# Thermostat_EEM.net
KiCad netlist of a schematic drawn in Altium Designer
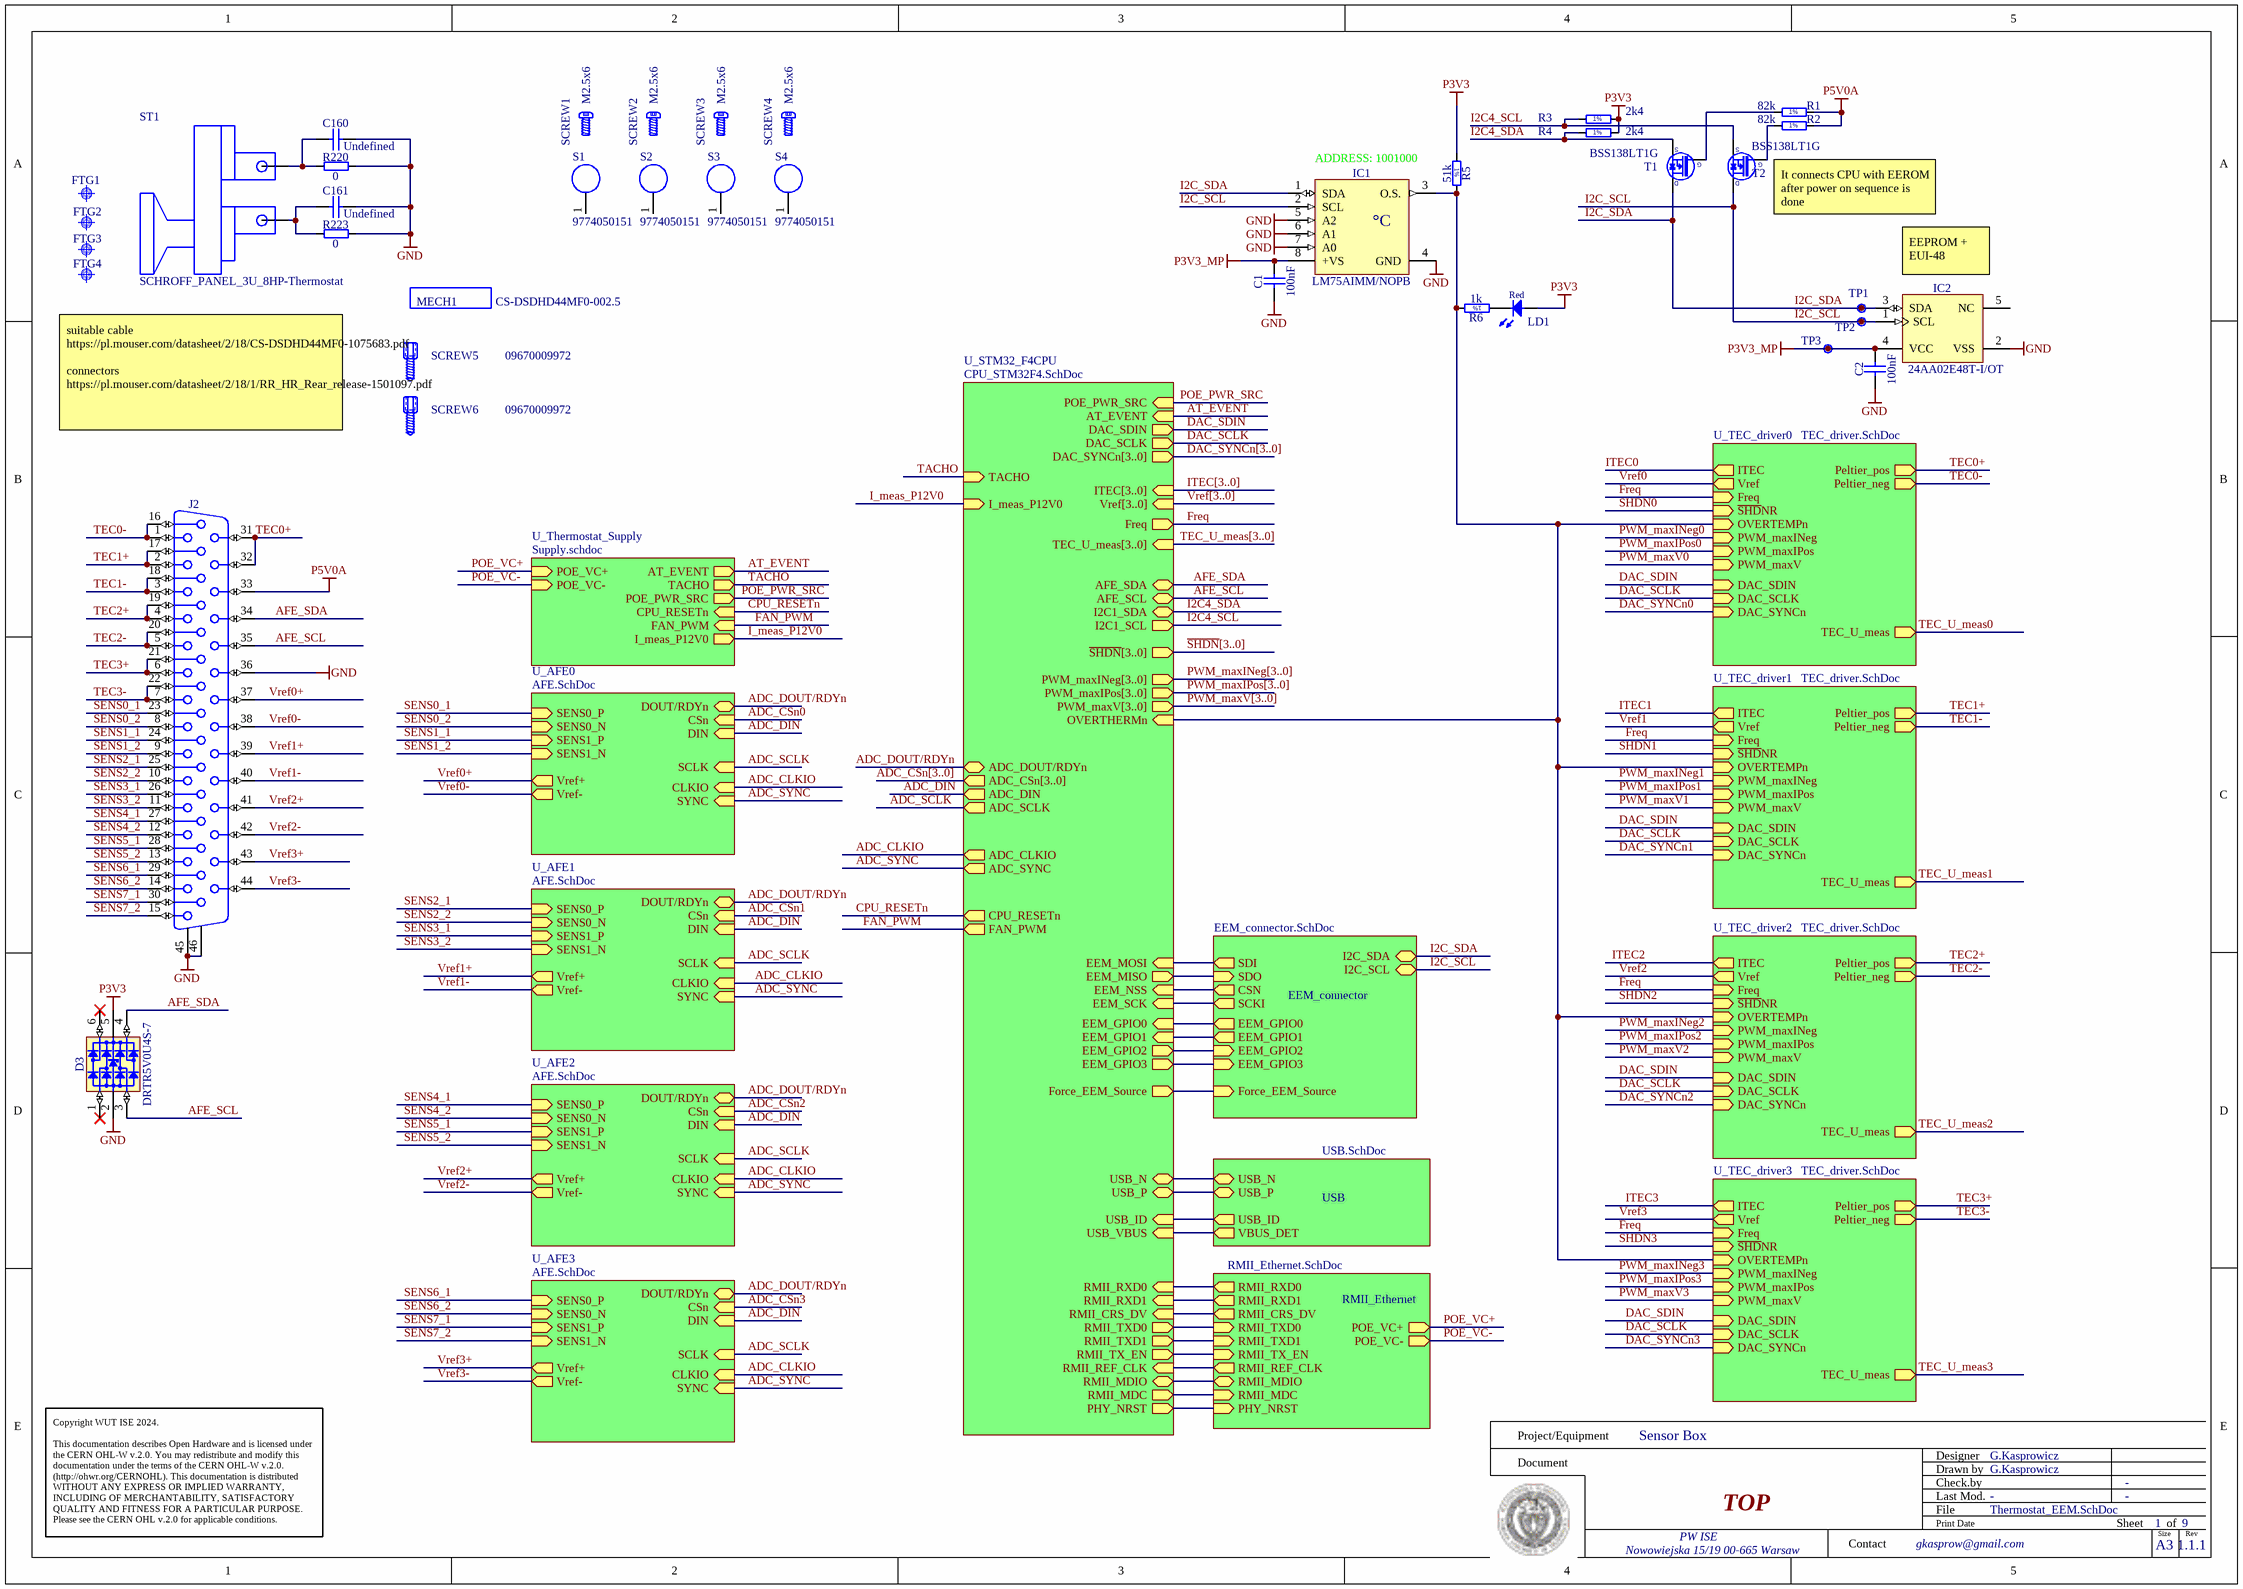
[diagram p0: Thermostat_EEM.SchDoc]

(export (version "E")
  (design (tool "Eeschema 10.0.6"))
  (components
    (comp (ref "C1")
      (value "100nF")
      (footprint "CAPC1005X55N")
      (description "Non-polarised capacitor")
      (fields
        (field (name "PART NUMBER") "CC0402_100NF_16V_10%_X5R")
        (field (name "VOLTAGE") "16V")
        (field (name "AUTHOR") "CERN DEM JLC")
      )
      (libsource (lib "Capacitors") (part "Capacitor - non polarized"))
    )
    (comp (ref "C2")
      (value "100nF")
      (footprint "CAPC1005X55N")
      (description "Non-polarised capacitor")
      (fields
        (field (name "PART NUMBER") "CC0402_100NF_16V_10%_X5R")
        (field (name "VOLTAGE") "16V")
        (field (name "AUTHOR") "CERN DEM JLC")
      )
      (libsource (lib "Capacitors") (part "Capacitor - non polarized"))
    )
    (comp (ref "C160")
      (value "Undefined")
      (footprint "CAPC2012X135N")
      (description "Non-polarised capacitor")
      (fields (field (name "PART NUMBER") "CC0805_NO-VALUE") (field (name "AUTHOR") "CERN DEM JLC"))
      (libsource (lib "Capacitors") (part "Capacitor - non polarized"))
    )
    (comp (ref "C161")
      (value "Undefined")
      (footprint "CAPC2012X135N")
      (description "Non-polarised capacitor")
      (fields (field (name "PART NUMBER") "CC0805_NO-VALUE") (field (name "AUTHOR") "CERN DEM JLC"))
      (libsource (lib "Capacitors") (part "Capacitor - non polarized"))
    )
    (comp (ref "D3")
      (value "DRTR5V0U4S-7")
      (footprint "SOT65P210X110-6N")
      (description "Integrated Quad Ultra-Low Capacitance ESD Protection")
      (fields (field (name "MANUFACTURER") "DIODES") (field (name "AUTHOR") "GK"))
      (libsource (lib "Diodes") (part "D_TVS_DRTR5V0U4S-7"))
    )
    (comp (ref "FTG1")
      (value "Use only in PCB")
      (footprint "FIDUCIAL_TOP_S100-200")
      (description "Fiducial Target")
      (fields (field (name "PART NUMBER") "FIDUCIAL_TARGET_S100-200") (field (name "AUTHOR") "CERN DEM JLC"))
      (libsource (lib "Eletro-mechanical") (part "Fiducial Target"))
    )
    (comp (ref "FTG2")
      (value "Use only in PCB")
      (footprint "FIDUCIAL_TOP_S100-200")
      (description "Fiducial Target")
      (fields (field (name "PART NUMBER") "FIDUCIAL_TARGET_S100-200") (field (name "AUTHOR") "CERN DEM JLC"))
      (libsource (lib "Eletro-mechanical") (part "Fiducial Target"))
    )
    (comp (ref "FTG3")
      (value "Use only in PCB")
      (footprint "FIDUCIAL_TOP_S100-200")
      (description "Fiducial Target")
      (fields (field (name "PART NUMBER") "FIDUCIAL_TARGET_S100-200") (field (name "AUTHOR") "CERN DEM JLC"))
      (libsource (lib "Eletro-mechanical") (part "Fiducial Target"))
    )
    (comp (ref "FTG4")
      (value "Use only in PCB")
      (footprint "FIDUCIAL_TOP_S100-200")
      (description "Fiducial Target")
      (fields (field (name "PART NUMBER") "FIDUCIAL_TARGET_S100-200") (field (name "AUTHOR") "CERN DEM JLC"))
      (libsource (lib "Eletro-mechanical") (part "Fiducial Target"))
    )
    (comp (ref "IC1")
      (value "LM75AIMM/NOPB")
      (footprint "SOP65P490X109-8N")
      (description "Digital Temperature Sensor and Thermal Watchdog with Two-Wire Interface")
      (fields (field (name "MANUFACTURER") "TEXAS INSTRUMENTS") (field (name "AUTHOR") "CERN DEM JLC"))
      (libsource (lib "ICs And Semiconductors") (part "LM75"))
    )
    (comp (ref "IC2")
      (value "24AA02E48T-I/OT")
      (footprint "SOT95P280X145-5N")
      (description "1.7V-5.5V, 2K I2C Serial EEPROM With EUI-48 Node Identity")
      (fields (field (name "MANUFACTURER") "MICROCHIP TECHNOLOGY") (field (name "AUTHOR") "CERN DEM MR"))
      (libsource (lib "ICs And Semiconductors") (part "24AA02E48T-I/OT"))
    )
    (comp (ref "J2")
      (value "D-Sub")
      (footprint "AMPHENOL_ICD44S13E6GX00LF")
      (description "Connector D-sub 44 Female")
      (fields
        (field (name "PART NUMBER") "AMPHENOL_ICD44S13E6GX00LF")
        (field (name "MANUFACTURER") "AMPHENOL")
        (field (name "AUTHOR") "CERN DEM BC")
      )
      (libsource (lib "Connectors") (part "Connector D-sub 44 Female"))
    )
    (comp (ref "LD1")
      (value "Red")
      (footprint "LED_KINGBRIGHT_KPH-1608SURCK")
      (description "LED Red 1C 2A")
      (fields
        (field (name "PART NUMBER") "LED_KINGBRIGHT_KPH-1608SURCK")
        (field (name "MANUFACTURER") "KINGBRIGHT")
        (field (name "AUTHOR") "CERN DEM JLC")
      )
      (libsource (lib "ICs And Semiconductors") (part "LED Red 1C 2A"))
    )
    (comp (ref "MECH1")
      (value "CS-DSDHD44MF0-002.5")
      (description "D-Sub Cables DELUXE HD44 M/F MOLDED 2.5'")
      (fields (field (name "MANUFACTURER") "Amphenol") (field (name "AUTHOR") "GK"))
      (libsource (lib "Mechanical") (part "Generic_mechanical"))
    )
    (comp (ref "R1")
      (value "82k")
      (footprint "RESC1608X55N")
      (description "Resistor - 1%")
      (fields
        (field (name "PART NUMBER") "R0603_82K_1%_0.1W_100PPM")
        (field (name "POWER") "0.1W")
        (field (name "AUTHOR") "CERN DEM JLC")
      )
      (libsource (lib "Resistors") (part "Resistor - 1%"))
    )
    (comp (ref "R2")
      (value "82k")
      (footprint "RESC1608X55N")
      (description "Resistor - 1%")
      (fields
        (field (name "PART NUMBER") "R0603_82K_1%_0.1W_100PPM")
        (field (name "POWER") "0.1W")
        (field (name "AUTHOR") "CERN DEM JLC")
      )
      (libsource (lib "Resistors") (part "Resistor - 1%"))
    )
    (comp (ref "R3")
      (value "2k4")
      (footprint "RESC1005X40N")
      (description "Resistor - 1%")
      (fields
        (field (name "PART NUMBER") "R0402_2K4_1%_0.0625W_100PPM")
        (field (name "POWER") "0.0625W")
        (field (name "AUTHOR") "CERN DEM JLC")
      )
      (libsource (lib "Resistors") (part "Resistor - 1%"))
    )
    (comp (ref "R4")
      (value "2k4")
      (footprint "RESC1005X40N")
      (description "Resistor - 1%")
      (fields
        (field (name "PART NUMBER") "R0402_2K4_1%_0.0625W_100PPM")
        (field (name "POWER") "0.0625W")
        (field (name "AUTHOR") "CERN DEM JLC")
      )
      (libsource (lib "Resistors") (part "Resistor - 1%"))
    )
    (comp (ref "R5")
      (value "51k")
      (footprint "RESC1005X40N")
      (description "Resistor - 1%")
      (fields
        (field (name "PART NUMBER") "R0402_51K_1%_0.0625W_100PPM")
        (field (name "POWER") "0.0625W")
        (field (name "AUTHOR") "CERN DEM JLC")
      )
      (libsource (lib "Resistors") (part "Resistor - 1%"))
    )
    (comp (ref "R6")
      (value "1k")
      (footprint "RESC1005X40N")
      (description "Resistor - 1%")
      (fields
        (field (name "PART NUMBER") "R0402_1K_1%_0.0625W_100PPM")
        (field (name "POWER") "0.0625W")
        (field (name "AUTHOR") "CERN DEM JLC")
      )
      (libsource (lib "Resistors") (part "Resistor - 1%"))
    )
    (comp (ref "R220")
      (value "0")
      (footprint "RESC1005X40N")
      (description "Resistor")
      (fields
        (field (name "PART NUMBER") "R0402_0R_JUMPER")
        (field (name "MANUFACTURER") "GENERIC")
        (field (name "AUTHOR") "CERN DEM JLC")
      )
      (libsource (lib "Resistors") (part "Resistor"))
    )
    (comp (ref "R223")
      (value "0")
      (footprint "RESC1005X40N")
      (description "Resistor")
      (fields
        (field (name "PART NUMBER") "R0402_0R_JUMPER")
        (field (name "MANUFACTURER") "GENERIC")
        (field (name "AUTHOR") "CERN DEM JLC")
      )
      (libsource (lib "Resistors") (part "Resistor"))
    )
    (comp (ref "S1")
      (value "9774050151")
      (footprint "9774050151")
      (description "WA-SMSI SMD Steel Spacer with internal Thread")
      (fields (field (name "MANUFACTURER") "Wurth Elektronik") (field (name "CREATED BY") "Baojun Chen"))
      (libsource (lib "Altium_SMSI_SMT_STEEL_SPACER_M2_5_THREAD_INTERNAL_rev15a") (part "WA-SMSI,  9774050151"))
    )
    (comp (ref "S2")
      (value "9774050151")
      (footprint "9774050151")
      (description "WA-SMSI SMD Steel Spacer with internal Thread")
      (fields (field (name "MANUFACTURER") "Wurth Elektronik") (field (name "CREATED BY") "Baojun Chen"))
      (libsource (lib "Altium_SMSI_SMT_STEEL_SPACER_M2_5_THREAD_INTERNAL_rev15a") (part "WA-SMSI,  9774050151"))
    )
    (comp (ref "S3")
      (value "9774050151")
      (footprint "9774050151")
      (description "WA-SMSI SMD Steel Spacer with internal Thread")
      (fields (field (name "MANUFACTURER") "Wurth Elektronik") (field (name "CREATED BY") "Baojun Chen"))
      (libsource (lib "Altium_SMSI_SMT_STEEL_SPACER_M2_5_THREAD_INTERNAL_rev15a") (part "WA-SMSI,  9774050151"))
    )
    (comp (ref "S4")
      (value "9774050151")
      (footprint "9774050151")
      (description "WA-SMSI SMD Steel Spacer with internal Thread")
      (fields (field (name "MANUFACTURER") "Wurth Elektronik") (field (name "CREATED BY") "Baojun Chen"))
      (libsource (lib "Altium_SMSI_SMT_STEEL_SPACER_M2_5_THREAD_INTERNAL_rev15a") (part "WA-SMSI,  9774050151"))
    )
    (comp (ref "SCREW1")
      (value "M2.5x6")
      (footprint "BOSSARD_BN5687-3061597_h")
      (description "Screw")
      (fields
        (field (name "PART NUMBER") "BOSSARD_BN5687-3061597_h")
        (field (name "MANUFACTURER") "BOSSARD")
        (field (name "AUTHOR") "CERN DEM JLC")
      )
      (libsource (lib "Eletro-mechanical") (part "Screw"))
    )
    (comp (ref "SCREW2")
      (value "M2.5x6")
      (footprint "BOSSARD_BN5687-3061597_h")
      (description "Screw")
      (fields
        (field (name "PART NUMBER") "BOSSARD_BN5687-3061597_h")
        (field (name "MANUFACTURER") "BOSSARD")
        (field (name "AUTHOR") "CERN DEM JLC")
      )
      (libsource (lib "Eletro-mechanical") (part "Screw"))
    )
    (comp (ref "SCREW3")
      (value "M2.5x6")
      (footprint "BOSSARD_BN5687-3061597_h")
      (description "Screw")
      (fields
        (field (name "PART NUMBER") "BOSSARD_BN5687-3061597_h")
        (field (name "MANUFACTURER") "BOSSARD")
        (field (name "AUTHOR") "CERN DEM JLC")
      )
      (libsource (lib "Eletro-mechanical") (part "Screw"))
    )
    (comp (ref "SCREW4")
      (value "M2.5x6")
      (footprint "BOSSARD_BN5687-3061597_h")
      (description "Screw")
      (fields
        (field (name "PART NUMBER") "BOSSARD_BN5687-3061597_h")
        (field (name "MANUFACTURER") "BOSSARD")
        (field (name "AUTHOR") "CERN DEM JLC")
      )
      (libsource (lib "Eletro-mechanical") (part "Screw"))
    )
    (comp (ref "SCREW5")
      (value "09670009972")
      (footprint "3M_3341-31")
      (description "Female Screw Lock")
      (fields (field (name "MANUFACTURER") "HARTING") (field (name "AUTHOR") "GK"))
      (libsource (lib "Mechanical") (part "MECH_MDR_screw_lock"))
    )
    (comp (ref "SCREW6")
      (value "09670009972")
      (footprint "3M_3341-31")
      (description "Female Screw Lock")
      (fields (field (name "MANUFACTURER") "HARTING") (field (name "AUTHOR") "GK"))
      (libsource (lib "Mechanical") (part "MECH_MDR_screw_lock"))
    )
    (comp (ref "ST1")
      (value "SCHROFF_PANEL_3U_8HP-Thermostat")
      (footprint "SCHROFF_PANEL_3HP_4U - Thermostat")
      (description "Schroff 8HP 3U EUROCARD Panel")
      (fields (field (name "MANUFACTURER") "Schroff") (field (name "MANUFACTURER PART NUMBER") "20848-668"))
      (libsource (lib "Mechanical") (part "SCHROFF_PANEL_3U_4HP_Thermostat"))
    )
    (comp (ref "T1")
      (value "BSS138LT1G")
      (footprint "SOT95P240X110-3N")
      (description "N-CHANNEL MOSFET WITH DIODE")
      (fields (field (name "MANUFACTURER") "ON SEMICONDUCTOR") (field (name "AUTHOR") "CERN DEM JLC"))
      (libsource (lib "ICs And Semiconductors") (part "N-MOSFET-D 1G 2S 3D"))
    )
    (comp (ref "T2")
      (value "BSS138LT1G")
      (footprint "SOT95P240X110-3N")
      (description "N-CHANNEL MOSFET WITH DIODE")
      (fields (field (name "MANUFACTURER") "ON SEMICONDUCTOR") (field (name "AUTHOR") "CERN DEM JLC"))
      (libsource (lib "ICs And Semiconductors") (part "N-MOSFET-D 1G 2S 3D"))
    )
    (comp (ref "TP1")
      (value "Test Point")
      (footprint "TPS127")
      (fields (field (name "PART NUMBER") "SMD_PAD_1.27X1.27MM") (field (name "AUTHOR") "CERN DEM JLC"))
      (libsource (lib "Eletro-mechanical") (part "Test Point"))
    )
    (comp (ref "TP2")
      (value "Test Point")
      (footprint "TPS127")
      (fields (field (name "PART NUMBER") "SMD_PAD_1.27X1.27MM") (field (name "AUTHOR") "CERN DEM JLC"))
      (libsource (lib "Eletro-mechanical") (part "Test Point"))
    )
    (comp (ref "TP3")
      (value "Test Point")
      (footprint "TPS127")
      (fields (field (name "PART NUMBER") "SMD_PAD_1.27X1.27MM") (field (name "AUTHOR") "CERN DEM JLC"))
      (libsource (lib "Eletro-mechanical") (part "Test Point"))
    )
  )
  (nets
    (net (code "11") (name "/AFE_SCL") (class "Default")
      (node (ref "D3") (pin "3") (pinfunction "I/O2_3") (pintype "bidirectional"))
      (node (ref "J2") (pin "35") (pinfunction "35_35") (pintype "bidirectional"))
    )
    (net (code "12") (name "/AFE_SDA") (class "Default")
      (node (ref "D3") (pin "4") (pinfunction "I/O3_4") (pintype "bidirectional"))
      (node (ref "J2") (pin "34") (pinfunction "34_34") (pintype "bidirectional"))
    )
    (net (code "31") (name "/I2C4_SCL") (class "Default")
      (node (ref "R3") (pin "1") (pinfunction "1_1") (pintype "passive"))
      (node (ref "T2") (pin "2") (pinfunction "S_2") (pintype "passive"))
    )
    (net (code "32") (name "/I2C4_SDA") (class "Default")
      (node (ref "R4") (pin "1") (pinfunction "1_1") (pintype "passive"))
      (node (ref "T1") (pin "2") (pinfunction "S_2") (pintype "passive"))
    )
    (net (code "33") (name "/I2C_SCL") (class "Default")
      (node (ref "IC1") (pin "2") (pinfunction "SCL_2") (pintype "input"))
      (node (ref "IC2") (pin "1") (pinfunction "SCL_1") (pintype "input"))
      (node (ref "T2") (pin "3") (pinfunction "D_3") (pintype "passive"))
      (node (ref "TP2") (pin "1") (pinfunction "1_1") (pintype "bidirectional"))
    )
    (net (code "34") (name "/I2C_SDA") (class "Default")
      (node (ref "IC1") (pin "1") (pinfunction "SDA_1") (pintype "bidirectional"))
      (node (ref "IC2") (pin "3") (pinfunction "SDA_3") (pintype "bidirectional"))
      (node (ref "T1") (pin "3") (pinfunction "D_3") (pintype "passive"))
      (node (ref "TP1") (pin "1") (pinfunction "1_1") (pintype "bidirectional"))
    )
    (net (code "41") (name "/OVERTEMPn") (class "Default")
      (node (ref "IC1") (pin "3") (pinfunction "O.S._3") (pintype "output"))
      (node (ref "R5") (pin "2") (pinfunction "2_2") (pintype "passive"))
      (node (ref "R6") (pin "2") (pinfunction "2_2") (pintype "passive"))
    )
    (net (code "72") (name "/SENS0_1") (class "Default")
      (node (ref "J2") (pin "23") (pinfunction "23_23") (pintype "bidirectional"))
    )
    (net (code "73") (name "/SENS0_2") (class "Default")
      (node (ref "J2") (pin "8") (pinfunction "8_8") (pintype "bidirectional"))
    )
    (net (code "74") (name "/SENS1_1") (class "Default")
      (node (ref "J2") (pin "24") (pinfunction "24_24") (pintype "bidirectional"))
    )
    (net (code "75") (name "/SENS1_2") (class "Default")
      (node (ref "J2") (pin "9") (pinfunction "9_9") (pintype "bidirectional"))
    )
    (net (code "76") (name "/SENS2_1") (class "Default")
      (node (ref "J2") (pin "25") (pinfunction "25_25") (pintype "bidirectional"))
    )
    (net (code "77") (name "/SENS2_2") (class "Default")
      (node (ref "J2") (pin "10") (pinfunction "10_10") (pintype "bidirectional"))
    )
    (net (code "78") (name "/SENS3_1") (class "Default")
      (node (ref "J2") (pin "26") (pinfunction "26_26") (pintype "bidirectional"))
    )
    (net (code "79") (name "/SENS3_2") (class "Default")
      (node (ref "J2") (pin "11") (pinfunction "11_11") (pintype "bidirectional"))
    )
    (net (code "80") (name "/SENS4_1") (class "Default")
      (node (ref "J2") (pin "27") (pinfunction "27_27") (pintype "bidirectional"))
    )
    (net (code "81") (name "/SENS4_2") (class "Default")
      (node (ref "J2") (pin "12") (pinfunction "12_12") (pintype "bidirectional"))
    )
    (net (code "82") (name "/SENS5_1") (class "Default")
      (node (ref "J2") (pin "28") (pinfunction "28_28") (pintype "bidirectional"))
    )
    (net (code "83") (name "/SENS5_2") (class "Default")
      (node (ref "J2") (pin "13") (pinfunction "13_13") (pintype "bidirectional"))
    )
    (net (code "84") (name "/SENS6_1") (class "Default")
      (node (ref "J2") (pin "29") (pinfunction "29_29") (pintype "bidirectional"))
    )
    (net (code "85") (name "/SENS6_2") (class "Default")
      (node (ref "J2") (pin "14") (pinfunction "14_14") (pintype "bidirectional"))
    )
    (net (code "86") (name "/SENS7_1") (class "Default")
      (node (ref "J2") (pin "30") (pinfunction "30_30") (pintype "bidirectional"))
    )
    (net (code "87") (name "/SENS7_2") (class "Default")
      (node (ref "J2") (pin "15") (pinfunction "15_15") (pintype "bidirectional"))
    )
    (net (code "89") (name "/TEC0+") (class "Default")
      (node (ref "J2") (pin "31") (pinfunction "31_31") (pintype "bidirectional"))
      (node (ref "J2") (pin "32") (pinfunction "32_32") (pintype "bidirectional"))
    )
    (net (code "90") (name "/TEC0-") (class "Default")
      (node (ref "J2") (pin "1") (pinfunction "1_1") (pintype "bidirectional"))
      (node (ref "J2") (pin "16") (pinfunction "16_16") (pintype "bidirectional"))
    )
    (net (code "91") (name "/TEC1+") (class "Default")
      (node (ref "J2") (pin "17") (pinfunction "17_17") (pintype "bidirectional"))
      (node (ref "J2") (pin "2") (pinfunction "2_2") (pintype "bidirectional"))
    )
    (net (code "92") (name "/TEC1-") (class "Default")
      (node (ref "J2") (pin "18") (pinfunction "18_18") (pintype "bidirectional"))
      (node (ref "J2") (pin "3") (pinfunction "3_3") (pintype "bidirectional"))
    )
    (net (code "93") (name "/TEC2+") (class "Default")
      (node (ref "J2") (pin "19") (pinfunction "19_19") (pintype "bidirectional"))
      (node (ref "J2") (pin "4") (pinfunction "4_4") (pintype "bidirectional"))
    )
    (net (code "94") (name "/TEC2-") (class "Default")
      (node (ref "J2") (pin "20") (pinfunction "20_20") (pintype "bidirectional"))
      (node (ref "J2") (pin "5") (pinfunction "5_5") (pintype "bidirectional"))
    )
    (net (code "95") (name "/TEC3+") (class "Default")
      (node (ref "J2") (pin "21") (pinfunction "21_21") (pintype "bidirectional"))
      (node (ref "J2") (pin "6") (pinfunction "6_6") (pintype "bidirectional"))
    )
    (net (code "96") (name "/TEC3-") (class "Default")
      (node (ref "J2") (pin "22") (pinfunction "22_22") (pintype "bidirectional"))
      (node (ref "J2") (pin "7") (pinfunction "7_7") (pintype "bidirectional"))
    )
    (net (code "107") (name "/Vref0+") (class "Default")
      (node (ref "J2") (pin "37") (pinfunction "37_37") (pintype "bidirectional"))
    )
    (net (code "108") (name "/Vref0-") (class "Default")
      (node (ref "J2") (pin "38") (pinfunction "38_38") (pintype "bidirectional"))
    )
    (net (code "110") (name "/Vref1+") (class "Default")
      (node (ref "J2") (pin "39") (pinfunction "39_39") (pintype "bidirectional"))
    )
    (net (code "111") (name "/Vref1-") (class "Default")
      (node (ref "J2") (pin "40") (pinfunction "40_40") (pintype "bidirectional"))
    )
    (net (code "113") (name "/Vref2+") (class "Default")
      (node (ref "J2") (pin "41") (pinfunction "41_41") (pintype "bidirectional"))
    )
    (net (code "114") (name "/Vref2-") (class "Default")
      (node (ref "J2") (pin "42") (pinfunction "42_42") (pintype "bidirectional"))
    )
    (net (code "116") (name "/Vref3+") (class "Default")
      (node (ref "J2") (pin "43") (pinfunction "43_43") (pintype "bidirectional"))
    )
    (net (code "117") (name "/Vref3-") (class "Default")
      (node (ref "J2") (pin "44") (pinfunction "44_44") (pintype "bidirectional"))
    )
    (net (code "124") (name "GND") (class "Default")
      (node (ref "C1") (pin "1") (pinfunction "1_1") (pintype "passive"))
      (node (ref "C160") (pin "2") (pinfunction "2_2") (pintype "passive"))
      (node (ref "C161") (pin "2") (pinfunction "2_2") (pintype "passive"))
      (node (ref "C2") (pin "1") (pinfunction "1_1") (pintype "passive"))
      (node (ref "D3") (pin "2") (pinfunction "GND_2") (pintype "power_in"))
      (node (ref "IC1") (pin "4") (pinfunction "GND_4") (pintype "power_in"))
      (node (ref "IC1") (pin "5") (pinfunction "A2_5") (pintype "input"))
      (node (ref "IC1") (pin "6") (pinfunction "A1_6") (pintype "input"))
      (node (ref "IC1") (pin "7") (pinfunction "A0_7") (pintype "input"))
      (node (ref "IC2") (pin "2") (pinfunction "VSS_2") (pintype "power_in"))
      (node (ref "J2") (pin "36") (pinfunction "36_36") (pintype "bidirectional"))
      (node (ref "J2") (pin "45") (pinfunction "45_45") (pintype "passive"))
      (node (ref "J2") (pin "46") (pinfunction "46_46") (pintype "passive"))
      (node (ref "R220") (pin "2") (pinfunction "2_2") (pintype "passive"))
      (node (ref "R223") (pin "2") (pinfunction "2_2") (pintype "passive"))
    )
    (net (code "125") (name "Net-(C160-Pad1)") (class "Default")
      (node (ref "C160") (pin "1") (pinfunction "1_1") (pintype "passive"))
      (node (ref "R220") (pin "1") (pinfunction "1_1") (pintype "passive"))
      (node (ref "ST1") (pin "1") (pinfunction "1_1") (pintype "passive"))
    )
    (net (code "126") (name "Net-(C161-Pad1)") (class "Default")
      (node (ref "C161") (pin "1") (pinfunction "1_1") (pintype "passive"))
      (node (ref "R223") (pin "1") (pinfunction "1_1") (pintype "passive"))
      (node (ref "ST1") (pin "0") (pinfunction "0_0") (pintype "passive"))
    )
    (net (code "127") (name "Net-(LD1-C)") (class "Default")
      (node (ref "LD1") (pin "1") (pinfunction "C_1") (pintype "passive"))
      (node (ref "R6") (pin "1") (pinfunction "1_1") (pintype "passive"))
    )
    (net (code "128") (name "Net-(T1-G)") (class "Default")
      (node (ref "R1") (pin "1") (pinfunction "1_1") (pintype "passive"))
      (node (ref "T1") (pin "1") (pinfunction "G_1") (pintype "passive"))
    )
    (net (code "129") (name "Net-(T2-G)") (class "Default")
      (node (ref "R2") (pin "1") (pinfunction "1_1") (pintype "passive"))
      (node (ref "T2") (pin "1") (pinfunction "G_1") (pintype "passive"))
    )
    (net (code "130") (name "P3V3") (class "Default")
      (node (ref "D3") (pin "5") (pinfunction "VBUS_5") (pintype "power_in"))
      (node (ref "LD1") (pin "2") (pinfunction "A_2") (pintype "passive"))
      (node (ref "R3") (pin "2") (pinfunction "2_2") (pintype "passive"))
      (node (ref "R4") (pin "2") (pinfunction "2_2") (pintype "passive"))
      (node (ref "R5") (pin "1") (pinfunction "1_1") (pintype "passive"))
    )
    (net (code "131") (name "P3V3_MP") (class "Default")
      (node (ref "C1") (pin "2") (pinfunction "2_2") (pintype "passive"))
      (node (ref "C2") (pin "2") (pinfunction "2_2") (pintype "passive"))
      (node (ref "IC1") (pin "8") (pinfunction "+VS_8") (pintype "power_in"))
      (node (ref "IC2") (pin "4") (pinfunction "VCC_4") (pintype "power_in"))
      (node (ref "TP3") (pin "1") (pinfunction "1_1") (pintype "bidirectional"))
    )
    (net (code "132") (name "P5V0A") (class "Default")
      (node (ref "J2") (pin "33") (pinfunction "33_33") (pintype "bidirectional"))
      (node (ref "R1") (pin "2") (pinfunction "2_2") (pintype "passive"))
      (node (ref "R2") (pin "2") (pinfunction "2_2") (pintype "passive"))
    )
    (net (code "133") (name "unconnected-(D3-I{slash}O1-Pad1)") (class "Default")
      (node (ref "D3") (pin "1") (pinfunction "I/O1_1") (pintype "bidirectional+no_connect"))
    )
    (net (code "134") (name "unconnected-(D3-I{slash}O4-Pad6)") (class "Default")
      (node (ref "D3") (pin "6") (pinfunction "I/O4_6") (pintype "bidirectional+no_connect"))
    )
    (net (code "135") (name "unconnected-(IC2-NC-Pad5)") (class "Default")
      (node (ref "IC2") (pin "5") (pinfunction "NC_5") (pintype "passive"))
    )
    (net (code "136") (name "unconnected-(S1-Pad1)") (class "Default")
      (node (ref "S1") (pin "1") (pinfunction "1_1") (pintype "passive"))
    )
    (net (code "137") (name "unconnected-(S2-Pad1)") (class "Default")
      (node (ref "S2") (pin "1") (pinfunction "1_1") (pintype "passive"))
    )
    (net (code "138") (name "unconnected-(S3-Pad1)") (class "Default")
      (node (ref "S3") (pin "1") (pinfunction "1_1") (pintype "passive"))
    )
    (net (code "139") (name "unconnected-(S4-Pad1)") (class "Default")
      (node (ref "S4") (pin "1") (pinfunction "1_1") (pintype "passive"))
    )
  )
)
